# POWER_B2.net
KiCad netlist of a schematic drawn in Altium Designer
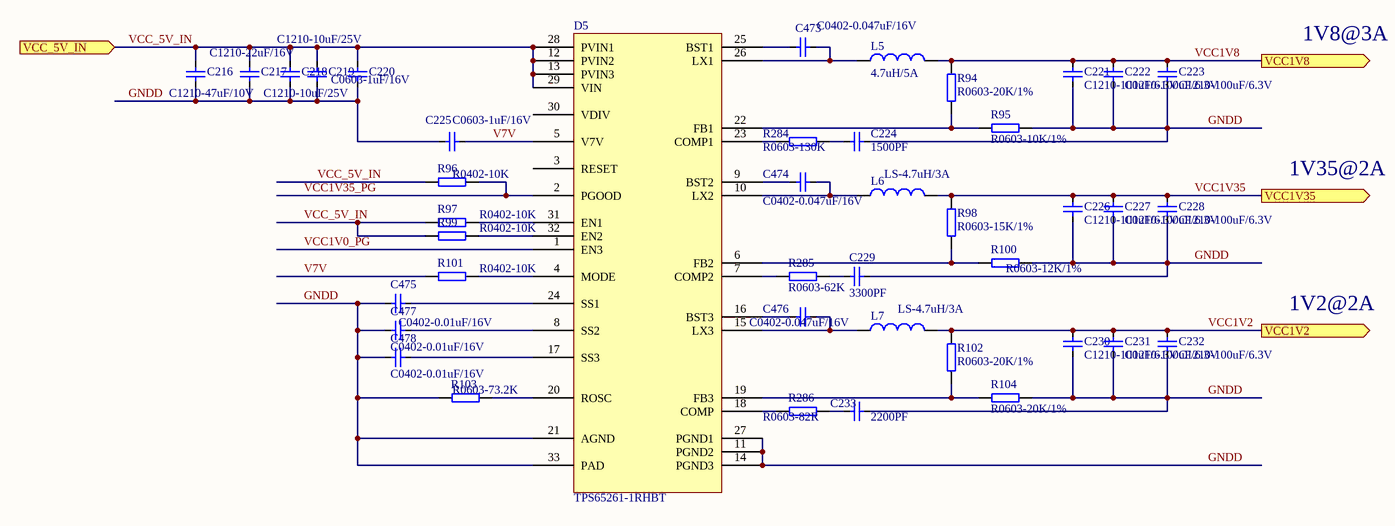
[diagram p0: POWER_B2.SchDoc]

(export (version "E")
  (design (tool "Eeschema 10.0.6"))
  (components
    (comp (ref "C216")
      (value "C1210-47uF/10V")
      (footprint "C1210")
      (fields (field (name "SCHEMATIC_PART") "CAP"))
      (libsource (lib "Database_Libs1") (part "CAP"))
    )
    (comp (ref "C217")
      (value "C1210-22uF/16V")
      (footprint "C1210")
      (fields (field (name "SCHEMATIC_PART") "CAP"))
      (libsource (lib "Database_Libs1") (part "CAP"))
    )
    (comp (ref "C218")
      (value "C1210-10uF/25V")
      (footprint "C1210")
      (fields (field (name "SCHEMATIC_PART") "CAP"))
      (libsource (lib "Database_Libs1") (part "CAP"))
    )
    (comp (ref "C219")
      (value "C1210-10uF/25V")
      (footprint "C1210")
      (fields (field (name "SCHEMATIC_PART") "CAP"))
      (libsource (lib "Database_Libs1") (part "CAP"))
    )
    (comp (ref "C220")
      (value "C0603-1uF/16V")
      (footprint "C0603")
      (description "X7R")
      (fields (field (name "SCHEMATIC_PART") "CAP"))
      (libsource (lib "Database_Libs1") (part "CAP"))
    )
    (comp (ref "C221")
      (value "C1210-100uF/6.3V")
      (footprint "C1210")
      (fields (field (name "SCHEMATIC_PART") "CAP"))
      (libsource (lib "Database_Libs1") (part "CAP"))
    )
    (comp (ref "C222")
      (value "C1210-100uF/6.3V")
      (footprint "C1210")
      (fields (field (name "SCHEMATIC_PART") "CAP"))
      (libsource (lib "Database_Libs1") (part "CAP"))
    )
    (comp (ref "C223")
      (value "C1210-100uF/6.3V")
      (footprint "C1210")
      (fields (field (name "SCHEMATIC_PART") "CAP"))
      (libsource (lib "Database_Libs1") (part "CAP"))
    )
    (comp (ref "C224")
      (value "1500PF")
      (footprint "C0603")
      (fields (field (name "SCHEMATIC_PART") "CAP"))
      (libsource (lib "Database_Libs1") (part "CAP"))
    )
    (comp (ref "C225")
      (value "C0603-1uF/16V")
      (footprint "C0603")
      (description "X7R")
      (fields (field (name "SCHEMATIC_PART") "CAP"))
      (libsource (lib "Database_Libs1") (part "CAP"))
    )
    (comp (ref "C226")
      (value "C1210-100uF/6.3V")
      (footprint "C1210")
      (fields (field (name "SCHEMATIC_PART") "CAP"))
      (libsource (lib "Database_Libs1") (part "CAP"))
    )
    (comp (ref "C227")
      (value "C1210-100uF/6.3V")
      (footprint "C1210")
      (fields (field (name "SCHEMATIC_PART") "CAP"))
      (libsource (lib "Database_Libs1") (part "CAP"))
    )
    (comp (ref "C228")
      (value "C1210-100uF/6.3V")
      (footprint "C1210")
      (fields (field (name "SCHEMATIC_PART") "CAP"))
      (libsource (lib "Database_Libs1") (part "CAP"))
    )
    (comp (ref "C229")
      (value "3300PF")
      (footprint "C0603")
      (fields (field (name "SCHEMATIC_PART") "CAP"))
      (libsource (lib "Database_Libs1") (part "CAP"))
    )
    (comp (ref "C230")
      (value "C1210-100uF/6.3V")
      (footprint "C1210")
      (fields (field (name "SCHEMATIC_PART") "CAP"))
      (libsource (lib "Database_Libs1") (part "CAP"))
    )
    (comp (ref "C231")
      (value "C1210-100uF/6.3V")
      (footprint "C1210")
      (fields (field (name "SCHEMATIC_PART") "CAP"))
      (libsource (lib "Database_Libs1") (part "CAP"))
    )
    (comp (ref "C232")
      (value "C1210-100uF/6.3V")
      (footprint "C1210")
      (fields (field (name "SCHEMATIC_PART") "CAP"))
      (libsource (lib "Database_Libs1") (part "CAP"))
    )
    (comp (ref "C233")
      (value "2200PF")
      (footprint "C0603")
      (fields (field (name "SCHEMATIC_PART") "CAP"))
      (libsource (lib "Database_Libs1") (part "CAP"))
    )
    (comp (ref "C473")
      (value "C0402-0.047uF/16V")
      (footprint "C0402")
      (description "X7R")
      (fields (field (name "SCHEMATIC_PART") "CAP") (field (name "MANUFACTURER") "SAMSUNG"))
      (libsource (lib "Database_Libs1") (part "CAP"))
    )
    (comp (ref "C474")
      (value "C0402-0.047uF/16V")
      (footprint "C0402")
      (description "X7R")
      (fields (field (name "SCHEMATIC_PART") "CAP") (field (name "MANUFACTURER") "SAMSUNG"))
      (libsource (lib "Database_Libs1") (part "CAP"))
    )
    (comp (ref "C475")
      (value "C0402-0.01uF/16V")
      (footprint "C0402")
      (description "X7R")
      (fields (field (name "SCHEMATIC_PART") "CAP") (field (name "MANUFACTURER") "SAMSUNG"))
      (libsource (lib "Database_Libs1") (part "CAP"))
    )
    (comp (ref "C476")
      (value "C0402-0.047uF/16V")
      (footprint "C0402")
      (description "X7R")
      (fields (field (name "SCHEMATIC_PART") "CAP") (field (name "MANUFACTURER") "SAMSUNG"))
      (libsource (lib "Database_Libs1") (part "CAP"))
    )
    (comp (ref "C477")
      (value "C0402-0.01uF/16V")
      (footprint "C0402")
      (description "X7R")
      (fields (field (name "SCHEMATIC_PART") "CAP") (field (name "MANUFACTURER") "SAMSUNG"))
      (libsource (lib "Database_Libs1") (part "CAP"))
    )
    (comp (ref "C478")
      (value "C0402-0.01uF/16V")
      (footprint "C0402")
      (description "X7R")
      (fields (field (name "SCHEMATIC_PART") "CAP") (field (name "MANUFACTURER") "SAMSUNG"))
      (libsource (lib "Database_Libs1") (part "CAP"))
    )
    (comp (ref "D5")
      (value "TPS65261-1RHBT")
      (footprint "QFN-32N")
      (libsource (lib "Schlib1") (part "TPS65261RHBT"))
    )
    (comp (ref "L5")
      (value "4.7uH/5A")
      (footprint "LSMD12-13X13")
      (fields (field (name "SCHEMATIC_PART") "INDUCTOR"))
      (libsource (lib "Database_Libs1") (part "INDUCTOR"))
    )
    (comp (ref "L6")
      (value "LS-4.7uH/3A")
      (footprint "FMJ-0630T")
      (description "7.3*6.6*3mm,4.7uH/5.5A,40mR,20%,TMP")
      (fields (field (name "SCHEMATIC_PART") "INDUCTOR") (field (name "MANUFACTURER") "TMP"))
      (libsource (lib "Database_Libs1") (part "INDUCTOR"))
    )
    (comp (ref "L7")
      (value "LS-4.7uH/3A")
      (footprint "FMJ-0630T")
      (description "7.3*6.6*3mm,4.7uH/5.5A,40mR,20%,TMP")
      (fields (field (name "SCHEMATIC_PART") "INDUCTOR") (field (name "MANUFACTURER") "TMP"))
      (libsource (lib "Database_Libs1") (part "INDUCTOR"))
    )
    (comp (ref "R94")
      (value "R0603-20K/1%")
      (footprint "R0603")
      (fields (field (name "SCHEMATIC_PART") "RES") (field (name "MANUFACTURER") "HKT"))
      (libsource (lib "Database_Libs1") (part "RES"))
    )
    (comp (ref "R95")
      (value "R0603-10K/1%")
      (footprint "R0603")
      (fields (field (name "SCHEMATIC_PART") "RES") (field (name "MANUFACTURER") "HKT"))
      (libsource (lib "Database_Libs1") (part "RES"))
    )
    (comp (ref "R96")
      (value "R0402-10K")
      (footprint "R0402")
      (fields (field (name "SCHEMATIC_PART") "RES") (field (name "MANUFACTURER") "SAMSUNG"))
      (libsource (lib "Database_Libs1") (part "RES"))
    )
    (comp (ref "R97")
      (value "R0402-10K")
      (footprint "R0402")
      (fields (field (name "SCHEMATIC_PART") "RES") (field (name "MANUFACTURER") "SAMSUNG"))
      (libsource (lib "Database_Libs1") (part "RES"))
    )
    (comp (ref "R98")
      (value "R0603-15K/1%")
      (footprint "R0603")
      (fields (field (name "SCHEMATIC_PART") "RES") (field (name "MANUFACTURER") "HKT"))
      (libsource (lib "Database_Libs1") (part "RES"))
    )
    (comp (ref "R99")
      (value "R0402-10K")
      (footprint "R0402")
      (fields (field (name "SCHEMATIC_PART") "RES") (field (name "MANUFACTURER") "SAMSUNG"))
      (libsource (lib "Database_Libs1") (part "RES"))
    )
    (comp (ref "R100")
      (value "R0603-12K/1%")
      (footprint "R0603")
      (fields (field (name "SCHEMATIC_PART") "RES") (field (name "MANUFACTURER") "HKT"))
      (libsource (lib "Database_Libs1") (part "RES"))
    )
    (comp (ref "R101")
      (value "R0402-10K")
      (footprint "R0402")
      (fields (field (name "SCHEMATIC_PART") "RES") (field (name "MANUFACTURER") "SAMSUNG"))
      (libsource (lib "Database_Libs1") (part "RES"))
    )
    (comp (ref "R102")
      (value "R0603-20K/1%")
      (footprint "R0603")
      (fields (field (name "SCHEMATIC_PART") "RES") (field (name "MANUFACTURER") "HKT"))
      (libsource (lib "Database_Libs1") (part "RES"))
    )
    (comp (ref "R103")
      (value "R0603-73.2K")
      (footprint "R0603")
      (fields (field (name "SCHEMATIC_PART") "RES") (field (name "MANUFACTURER") "HKT"))
      (libsource (lib "Database_Libs1") (part "RES"))
    )
    (comp (ref "R104")
      (value "R0603-20K/1%")
      (footprint "R0603")
      (fields (field (name "SCHEMATIC_PART") "RES") (field (name "MANUFACTURER") "HKT"))
      (libsource (lib "Database_Libs1") (part "RES"))
    )
    (comp (ref "R284")
      (value "R0603-130K")
      (footprint "R0603")
      (fields (field (name "SCHEMATIC_PART") "RES") (field (name "MANUFACTURER") "HKT"))
      (libsource (lib "Database_Libs1") (part "RES"))
    )
    (comp (ref "R285")
      (value "R0603-62K")
      (footprint "R0603")
      (fields (field (name "SCHEMATIC_PART") "RES") (field (name "MANUFACTURER") "HKT"))
      (libsource (lib "Database_Libs1") (part "RES"))
    )
    (comp (ref "R286")
      (value "R0603-82R")
      (footprint "R0603")
      (fields (field (name "SCHEMATIC_PART") "RES") (field (name "MANUFACTURER") "HKT"))
      (libsource (lib "Database_Libs1") (part "RES"))
    )
  )
  (nets
    (net (code "1") (name "/GNDD") (class "Default")
      (node (ref "C216") (pin "2") (pinfunction "2_2") (pintype "passive"))
      (node (ref "C217") (pin "2") (pinfunction "2_2") (pintype "passive"))
      (node (ref "C218") (pin "2") (pinfunction "2_2") (pintype "passive"))
      (node (ref "C219") (pin "2") (pinfunction "2_2") (pintype "passive"))
      (node (ref "C220") (pin "2") (pinfunction "2_2") (pintype "passive"))
      (node (ref "C221") (pin "2") (pinfunction "2_2") (pintype "passive"))
      (node (ref "C222") (pin "2") (pinfunction "2_2") (pintype "passive"))
      (node (ref "C223") (pin "2") (pinfunction "2_2") (pintype "passive"))
      (node (ref "C224") (pin "2") (pinfunction "2_2") (pintype "passive"))
      (node (ref "C225") (pin "1") (pinfunction "1_1") (pintype "passive"))
      (node (ref "C226") (pin "2") (pinfunction "2_2") (pintype "passive"))
      (node (ref "C227") (pin "2") (pinfunction "2_2") (pintype "passive"))
      (node (ref "C228") (pin "2") (pinfunction "2_2") (pintype "passive"))
      (node (ref "C229") (pin "2") (pinfunction "2_2") (pintype "passive"))
      (node (ref "C230") (pin "2") (pinfunction "2_2") (pintype "passive"))
      (node (ref "C231") (pin "2") (pinfunction "2_2") (pintype "passive"))
      (node (ref "C232") (pin "2") (pinfunction "2_2") (pintype "passive"))
      (node (ref "C233") (pin "2") (pinfunction "2_2") (pintype "passive"))
      (node (ref "C475") (pin "1") (pinfunction "1_1") (pintype "passive"))
      (node (ref "C477") (pin "1") (pinfunction "1_1") (pintype "passive"))
      (node (ref "C478") (pin "1") (pinfunction "1_1") (pintype "passive"))
      (node (ref "D5") (pin "11") (pinfunction "PGND2_11") (pintype "passive"))
      (node (ref "D5") (pin "14") (pinfunction "PGND3_14") (pintype "passive"))
      (node (ref "D5") (pin "21") (pinfunction "AGND_21") (pintype "passive"))
      (node (ref "D5") (pin "27") (pinfunction "PGND1_27") (pintype "passive"))
      (node (ref "D5") (pin "33") (pinfunction "PAD_33") (pintype "passive"))
      (node (ref "R100") (pin "2") (pintype "passive"))
      (node (ref "R103") (pin "1") (pintype "passive"))
      (node (ref "R104") (pin "2") (pintype "passive"))
      (node (ref "R95") (pin "2") (pintype "passive"))
    )
    (net (code "2") (name "/V7V") (class "Default")
      (node (ref "C225") (pin "2") (pinfunction "2_2") (pintype "passive"))
      (node (ref "D5") (pin "5") (pinfunction "V7V_5") (pintype "passive"))
      (node (ref "R101") (pin "1") (pintype "passive"))
    )
    (net (code "3") (name "/VCC1V0_PG") (class "Default")
      (node (ref "D5") (pin "1") (pinfunction "EN3_1") (pintype "passive"))
    )
    (net (code "4") (name "/VCC1V2") (class "Default")
      (node (ref "C230") (pin "1") (pinfunction "1_1") (pintype "passive"))
      (node (ref "C231") (pin "1") (pinfunction "1_1") (pintype "passive"))
      (node (ref "C232") (pin "1") (pinfunction "1_1") (pintype "passive"))
      (node (ref "L7") (pin "2") (pinfunction "2_2") (pintype "passive"))
      (node (ref "R102") (pin "2") (pintype "passive"))
    )
    (net (code "5") (name "/VCC1V8") (class "Default")
      (node (ref "C221") (pin "1") (pinfunction "1_1") (pintype "passive"))
      (node (ref "C222") (pin "1") (pinfunction "1_1") (pintype "passive"))
      (node (ref "C223") (pin "1") (pinfunction "1_1") (pintype "passive"))
      (node (ref "L5") (pin "2") (pinfunction "2_2") (pintype "passive"))
      (node (ref "R94") (pin "2") (pintype "passive"))
    )
    (net (code "6") (name "/VCC1V35") (class "Default")
      (node (ref "C226") (pin "1") (pinfunction "1_1") (pintype "passive"))
      (node (ref "C227") (pin "1") (pinfunction "1_1") (pintype "passive"))
      (node (ref "C228") (pin "1") (pinfunction "1_1") (pintype "passive"))
      (node (ref "L6") (pin "2") (pinfunction "2_2") (pintype "passive"))
      (node (ref "R98") (pin "2") (pintype "passive"))
    )
    (net (code "7") (name "/VCC1V35_PG") (class "Default")
      (node (ref "D5") (pin "2") (pinfunction "PGOOD_2") (pintype "passive"))
      (node (ref "R96") (pin "2") (pintype "passive"))
    )
    (net (code "8") (name "/VCC_5V_IN") (class "Default")
      (node (ref "C216") (pin "1") (pinfunction "1_1") (pintype "passive"))
      (node (ref "C217") (pin "1") (pinfunction "1_1") (pintype "passive"))
      (node (ref "C218") (pin "1") (pinfunction "1_1") (pintype "passive"))
      (node (ref "C219") (pin "1") (pinfunction "1_1") (pintype "passive"))
      (node (ref "C220") (pin "1") (pinfunction "1_1") (pintype "passive"))
      (node (ref "D5") (pin "12") (pinfunction "PVIN2_12") (pintype "passive"))
      (node (ref "D5") (pin "13") (pinfunction "PVIN3_13") (pintype "passive"))
      (node (ref "D5") (pin "28") (pinfunction "PVIN1_28") (pintype "passive"))
      (node (ref "D5") (pin "29") (pinfunction "VIN_29") (pintype "passive"))
      (node (ref "R96") (pin "1") (pintype "passive"))
      (node (ref "R97") (pin "1") (pintype "passive"))
      (node (ref "R99") (pin "1") (pintype "passive"))
    )
    (net (code "9") (name "Net-(C224-Pad1)") (class "Default")
      (node (ref "C224") (pin "1") (pinfunction "1_1") (pintype "passive"))
      (node (ref "R284") (pin "2") (pintype "passive"))
    )
    (net (code "10") (name "Net-(C229-Pad1)") (class "Default")
      (node (ref "C229") (pin "1") (pinfunction "1_1") (pintype "passive"))
      (node (ref "R285") (pin "2") (pintype "passive"))
    )
    (net (code "11") (name "Net-(C233-Pad1)") (class "Default")
      (node (ref "C233") (pin "1") (pinfunction "1_1") (pintype "passive"))
      (node (ref "R286") (pin "2") (pintype "passive"))
    )
    (net (code "12") (name "Net-(D5-BST1)") (class "Default")
      (node (ref "C473") (pin "1") (pinfunction "1_1") (pintype "passive"))
      (node (ref "D5") (pin "25") (pinfunction "BST1_25") (pintype "passive"))
    )
    (net (code "13") (name "Net-(D5-BST2)") (class "Default")
      (node (ref "C474") (pin "1") (pinfunction "1_1") (pintype "passive"))
      (node (ref "D5") (pin "9") (pinfunction "BST2_9") (pintype "passive"))
    )
    (net (code "14") (name "Net-(D5-BST3)") (class "Default")
      (node (ref "C476") (pin "1") (pinfunction "1_1") (pintype "passive"))
      (node (ref "D5") (pin "16") (pinfunction "BST3_16") (pintype "passive"))
    )
    (net (code "15") (name "Net-(D5-COMP)") (class "Default")
      (node (ref "D5") (pin "18") (pinfunction "COMP_18") (pintype "passive"))
      (node (ref "R286") (pin "1") (pintype "passive"))
    )
    (net (code "16") (name "Net-(D5-COMP1)") (class "Default")
      (node (ref "D5") (pin "23") (pinfunction "COMP1_23") (pintype "passive"))
      (node (ref "R284") (pin "1") (pintype "passive"))
    )
    (net (code "17") (name "Net-(D5-COMP2)") (class "Default")
      (node (ref "D5") (pin "7") (pinfunction "COMP2_7") (pintype "passive"))
      (node (ref "R285") (pin "1") (pintype "passive"))
    )
    (net (code "18") (name "Net-(D5-EN1)") (class "Default")
      (node (ref "D5") (pin "31") (pinfunction "EN1_31") (pintype "passive"))
      (node (ref "R97") (pin "2") (pintype "passive"))
    )
    (net (code "19") (name "Net-(D5-EN2)") (class "Default")
      (node (ref "D5") (pin "32") (pinfunction "EN2_32") (pintype "passive"))
      (node (ref "R99") (pin "2") (pintype "passive"))
    )
    (net (code "20") (name "Net-(D5-FB1)") (class "Default")
      (node (ref "D5") (pin "22") (pinfunction "FB1_22") (pintype "passive"))
      (node (ref "R94") (pin "1") (pintype "passive"))
      (node (ref "R95") (pin "1") (pintype "passive"))
    )
    (net (code "21") (name "Net-(D5-FB2)") (class "Default")
      (node (ref "D5") (pin "6") (pinfunction "FB2_6") (pintype "passive"))
      (node (ref "R100") (pin "1") (pintype "passive"))
      (node (ref "R98") (pin "1") (pintype "passive"))
    )
    (net (code "22") (name "Net-(D5-FB3)") (class "Default")
      (node (ref "D5") (pin "19") (pinfunction "FB3_19") (pintype "passive"))
      (node (ref "R102") (pin "1") (pintype "passive"))
      (node (ref "R104") (pin "1") (pintype "passive"))
    )
    (net (code "23") (name "Net-(D5-LX1)") (class "Default")
      (node (ref "C473") (pin "2") (pinfunction "2_2") (pintype "passive"))
      (node (ref "D5") (pin "26") (pinfunction "LX1_26") (pintype "passive"))
      (node (ref "L5") (pin "1") (pinfunction "1_1") (pintype "passive"))
    )
    (net (code "24") (name "Net-(D5-LX2)") (class "Default")
      (node (ref "C474") (pin "2") (pinfunction "2_2") (pintype "passive"))
      (node (ref "D5") (pin "10") (pinfunction "LX2_10") (pintype "passive"))
      (node (ref "L6") (pin "1") (pinfunction "1_1") (pintype "passive"))
    )
    (net (code "25") (name "Net-(D5-LX3)") (class "Default")
      (node (ref "C476") (pin "2") (pinfunction "2_2") (pintype "passive"))
      (node (ref "D5") (pin "15") (pinfunction "LX3_15") (pintype "passive"))
      (node (ref "L7") (pin "1") (pinfunction "1_1") (pintype "passive"))
    )
    (net (code "26") (name "Net-(D5-MODE)") (class "Default")
      (node (ref "D5") (pin "4") (pinfunction "MODE_4") (pintype "passive"))
      (node (ref "R101") (pin "2") (pintype "passive"))
    )
    (net (code "27") (name "Net-(D5-ROSC)") (class "Default")
      (node (ref "D5") (pin "20") (pinfunction "ROSC_20") (pintype "passive"))
      (node (ref "R103") (pin "2") (pintype "passive"))
    )
    (net (code "28") (name "Net-(D5-SS1)") (class "Default")
      (node (ref "C475") (pin "2") (pinfunction "2_2") (pintype "passive"))
      (node (ref "D5") (pin "24") (pinfunction "SS1_24") (pintype "passive"))
    )
    (net (code "29") (name "Net-(D5-SS2)") (class "Default")
      (node (ref "C477") (pin "2") (pinfunction "2_2") (pintype "passive"))
      (node (ref "D5") (pin "8") (pinfunction "SS2_8") (pintype "passive"))
    )
    (net (code "30") (name "Net-(D5-SS3)") (class "Default")
      (node (ref "C478") (pin "2") (pinfunction "2_2") (pintype "passive"))
      (node (ref "D5") (pin "17") (pinfunction "SS3_17") (pintype "passive"))
    )
    (net (code "31") (name "unconnected-(D5-RESET-Pad3)") (class "Default")
      (node (ref "D5") (pin "3") (pinfunction "RESET_3") (pintype "passive"))
    )
    (net (code "32") (name "unconnected-(D5-VDIV-Pad30)") (class "Default")
      (node (ref "D5") (pin "30") (pinfunction "VDIV_30") (pintype "passive"))
    )
  )
)
